# High_Current_H-Bridge.net
KiCad netlist of a schematic drawn in Altium Designer
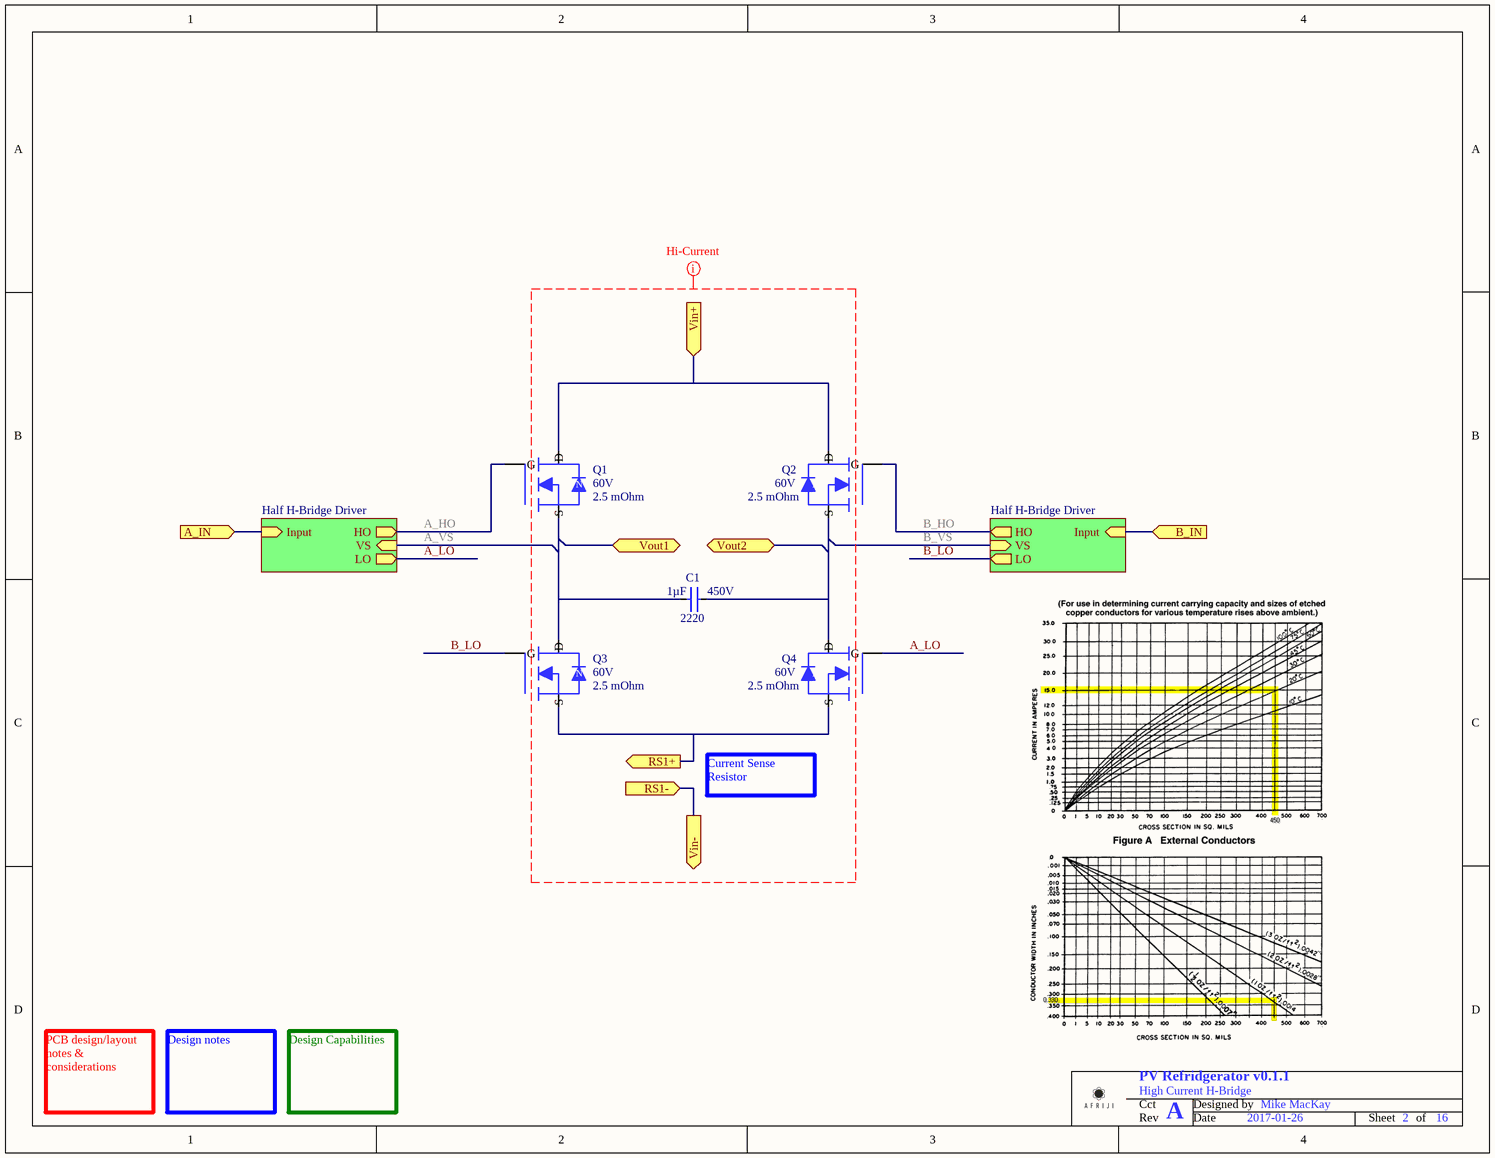
[diagram p0: High Current H-Bridge.SchDoc]

(export (version "E")
  (design (tool "Eeschema 10.0.6"))
  (components
    (comp (ref "C1")
      (value "1uF 2220 450V")
      (footprint "C2220 - Ceramic")
      (fields
        (field (name "MANUFACTURER") "TDK Corporation")
        (field (name "MANUFACTURER PART NUMBER") "CGA9P4X7T2W105M250KE")
        (field (name "TOLERANCE") "±20%")
        (field (name "CAPACITANCE") "1µF")
        (field (name "VOLTAGE - RATED") "450V")
        (field (name "PACKAGE / CASE") "2220")
      )
      (libsource (lib "Local Library") (part "1uF 2220 450V"))
    )
    (comp (ref "Q1")
      (value "N-MOSFET - 66A/25V")
      (footprint "DPAK")
      (fields
        (field (name "MANUFACTURER") "Infineon Technologies")
        (field (name "MANUFACTURER PART NUMBER") "IPD025N06N")
        (field (name "DRAIN TO SOURCE VOLTAGE (VDSS)") "60V")
        (field (name "RDS ON (MAX) @ ID, VGS") "2.5 mOhm")
      )
      (libsource (lib "Personal Library") (part "N-MOSFET - 66A/25V"))
    )
    (comp (ref "Q2")
      (value "N-MOSFET - 66A/25V")
      (footprint "DPAK")
      (fields
        (field (name "MANUFACTURER") "Infineon Technologies")
        (field (name "MANUFACTURER PART NUMBER") "IPD025N06N")
        (field (name "DRAIN TO SOURCE VOLTAGE (VDSS)") "60V")
        (field (name "RDS ON (MAX) @ ID, VGS") "2.5 mOhm")
      )
      (libsource (lib "Personal Library") (part "N-MOSFET - 66A/25V"))
    )
    (comp (ref "Q3")
      (value "N-MOSFET - 66A/25V")
      (footprint "DPAK")
      (fields
        (field (name "MANUFACTURER") "Infineon Technologies")
        (field (name "MANUFACTURER PART NUMBER") "IPD025N06N")
        (field (name "DRAIN TO SOURCE VOLTAGE (VDSS)") "60V")
        (field (name "RDS ON (MAX) @ ID, VGS") "2.5 mOhm")
      )
      (libsource (lib "Personal Library") (part "N-MOSFET - 66A/25V"))
    )
    (comp (ref "Q4")
      (value "N-MOSFET - 66A/25V")
      (footprint "DPAK")
      (fields
        (field (name "MANUFACTURER") "Infineon Technologies")
        (field (name "MANUFACTURER PART NUMBER") "IPD025N06N")
        (field (name "DRAIN TO SOURCE VOLTAGE (VDSS)") "60V")
        (field (name "RDS ON (MAX) @ ID, VGS") "2.5 mOhm")
      )
      (libsource (lib "Personal Library") (part "N-MOSFET - 66A/25V"))
    )
  )
  (nets
    (net (code "1") (name "/A_HO") (class "Default")
      (node (ref "Q1") (pin "1") (pinfunction "G_1") (pintype "passive"))
    )
    (net (code "3") (name "/A_LO") (class "Default")
      (node (ref "Q4") (pin "1") (pinfunction "G_1") (pintype "passive"))
    )
    (net (code "4") (name "/A_VS") (class "Default")
      (node (ref "C1") (pin "1") (pinfunction "1_1") (pintype "passive"))
      (node (ref "Q1") (pin "2") (pinfunction "S_2") (pintype "passive"))
      (node (ref "Q3") (pin "3") (pinfunction "D_3") (pintype "passive"))
    )
    (net (code "5") (name "/B_HO") (class "Default")
      (node (ref "Q2") (pin "1") (pinfunction "G_1") (pintype "passive"))
    )
    (net (code "7") (name "/B_LO") (class "Default")
      (node (ref "Q3") (pin "1") (pinfunction "G_1") (pintype "passive"))
    )
    (net (code "8") (name "/B_VS") (class "Default")
      (node (ref "C1") (pin "2") (pinfunction "2_2") (pintype "passive"))
      (node (ref "Q2") (pin "2") (pinfunction "S_2") (pintype "passive"))
      (node (ref "Q4") (pin "3") (pinfunction "D_3") (pintype "passive"))
    )
    (net (code "9") (name "/RS1+") (class "Default")
      (node (ref "Q3") (pin "2") (pinfunction "S_2") (pintype "passive"))
      (node (ref "Q4") (pin "2") (pinfunction "S_2") (pintype "passive"))
    )
    (net (code "11") (name "/Vin+") (class "Default")
      (node (ref "Q1") (pin "3") (pinfunction "D_3") (pintype "passive"))
      (node (ref "Q2") (pin "3") (pinfunction "D_3") (pintype "passive"))
    )
  )
)
